# SHDN-CURRENT-S02-V00-Microcontroller.net
KiCad netlist of a schematic drawn in Altium Designer
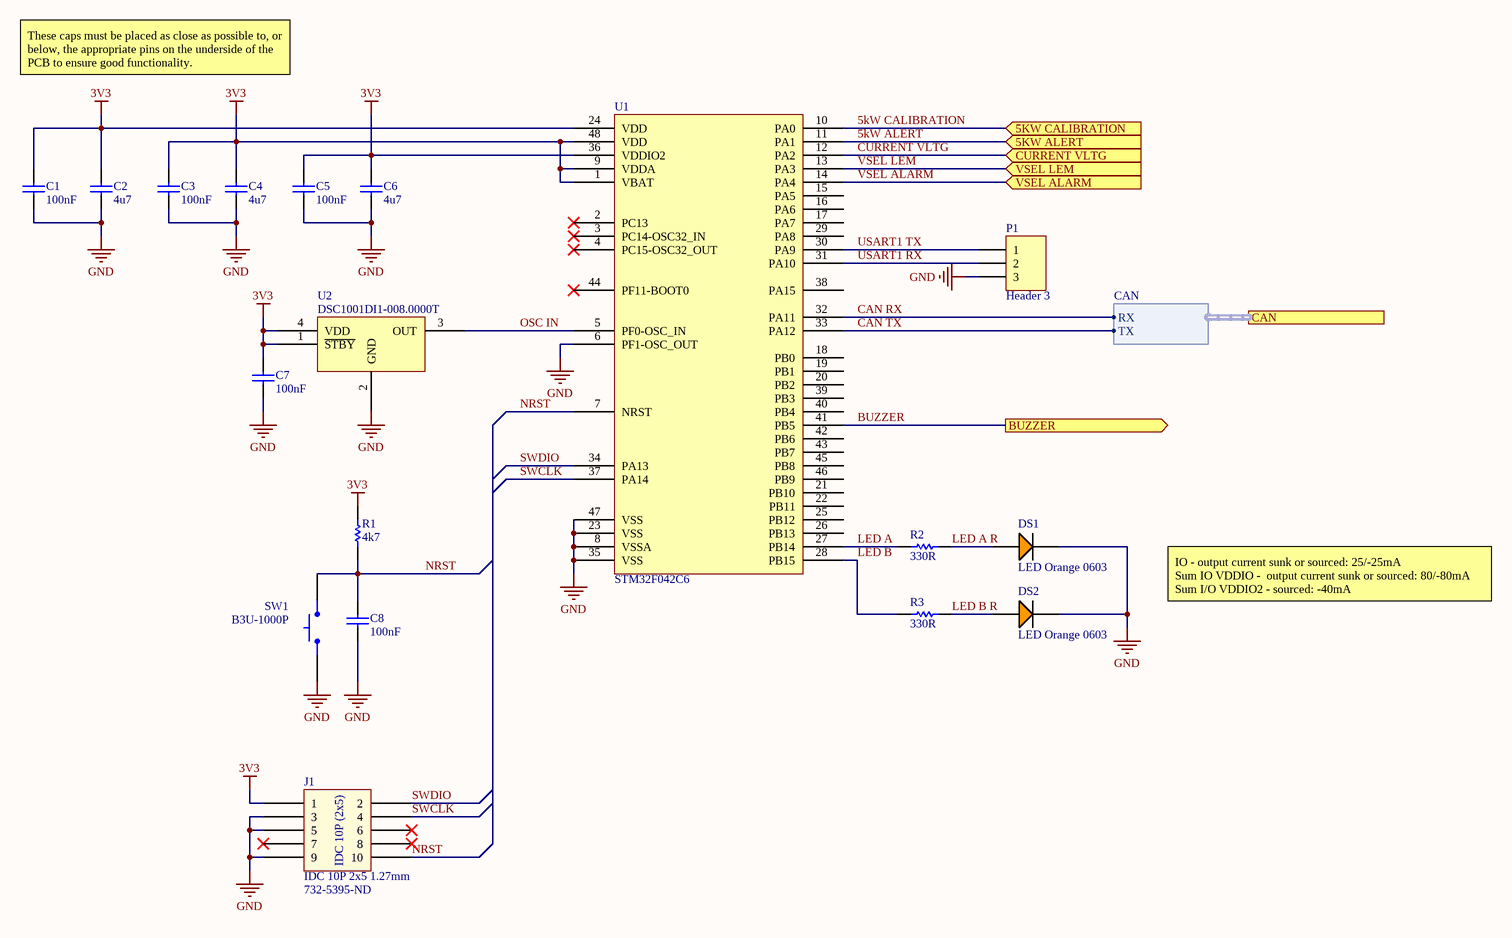
[diagram p0: SHDN-CURRENT-S02-V00-Microcontroller.SchDoc]

(export (version "E")
  (design (tool "Eeschema 10.0.6"))
  (components
    (comp (ref "C1")
      (value "100nF")
      (footprint "Cap_Ceramic_0603")
      (description "Capacitor, Ceramic, SMD, 100nF, 50V, 5%, X7R, 0603")
      (libsource (lib "StandardCapacitors") (part "100nF 50V 5% X7R 0603"))
    )
    (comp (ref "C2")
      (value "4u7")
      (footprint "Cap_Ceramic_0603")
      (description "Capacitor, Ceramic, SMD, 4u7, 50V, 5%, X7R, 0603")
      (libsource (lib "StandardCapacitors") (part "4u7 50V 5% X7R 0603"))
    )
    (comp (ref "C3")
      (value "100nF")
      (footprint "Cap_Ceramic_0603")
      (description "Capacitor, Ceramic, SMD, 100nF, 50V, 5%, X7R, 0603")
      (libsource (lib "StandardCapacitors") (part "100nF 50V 5% X7R 0603"))
    )
    (comp (ref "C4")
      (value "4u7")
      (footprint "Cap_Ceramic_0603")
      (description "Capacitor, Ceramic, SMD, 4u7, 50V, 5%, X7R, 0603")
      (libsource (lib "StandardCapacitors") (part "4u7 50V 5% X7R 0603"))
    )
    (comp (ref "C5")
      (value "100nF")
      (footprint "Cap_Ceramic_0603")
      (description "Capacitor, Ceramic, SMD, 100nF, 50V, 5%, X7R, 0603")
      (libsource (lib "StandardCapacitors") (part "100nF 50V 5% X7R 0603"))
    )
    (comp (ref "C6")
      (value "4u7")
      (footprint "Cap_Ceramic_0603")
      (description "Capacitor, Ceramic, SMD, 4u7, 50V, 5%, X7R, 0603")
      (libsource (lib "StandardCapacitors") (part "4u7 50V 5% X7R 0603"))
    )
    (comp (ref "C7")
      (value "100nF")
      (footprint "Cap_Ceramic_0603")
      (description "Capacitor, Ceramic, SMD, 100nF, 50V, 5%, X7R, 0603")
      (libsource (lib "StandardCapacitors") (part "100nF 50V 5% X7R 0603"))
    )
    (comp (ref "C8")
      (value "100nF")
      (footprint "Cap_Ceramic_0603")
      (description "Capacitor, Ceramic, SMD, 100nF, 50V, 5%, X7R, 0603")
      (libsource (lib "StandardCapacitors") (part "100nF 50V 5% X7R 0603"))
    )
    (comp (ref "DS1")
      (value "LED Orange 0603")
      (footprint "LED ORANGE 0603")
      (libsource (lib "QUTMS_LEDLibrary") (part "LED Orange 0603"))
    )
    (comp (ref "DS2")
      (value "LED Orange 0603")
      (footprint "LED ORANGE 0603")
      (libsource (lib "QUTMS_LEDLibrary") (part "LED Orange 0603"))
    )
    (comp (ref "J1")
      (value "IDC 10P 2x5 1.27mm")
      (footprint "IDC 1.27MM 10P")
      (libsource (lib "IDCConnectors") (part "IDC 10P 2x5 1.27mm"))
    )
    (comp (ref "P1")
      (value "Header 3")
      (footprint "HDR1X3")
      (description "Header, 3-Pin")
      (fields (field (name "PUBLISHER") "Altium Limited"))
      (libsource (lib "Miscellaneous Connectors") (part "Header 3"))
    )
    (comp (ref "R1")
      (value "4k7")
      (footprint "Res_ThinFilm_0603")
      (description "Resistor, SMD, 4k7, 0.1W, 5%, 0603")
      (libsource (lib "StandardResistors") (part "4k7 5% 0603"))
    )
    (comp (ref "R2")
      (value "330R")
      (footprint "Res_ThinFilm_0603")
      (description "Resistor, SMD, 330R, 0.1W, 5%, 0603")
      (libsource (lib "StandardResistors") (part "330R 5% 0603"))
    )
    (comp (ref "R3")
      (value "330R")
      (footprint "Res_ThinFilm_0603")
      (description "Resistor, SMD, 330R, 0.1W, 5%, 0603")
      (libsource (lib "StandardResistors") (part "330R 5% 0603"))
    )
    (comp (ref "SW1")
      (value "B3U-1000P")
      (footprint "BTN B3U-1000P")
      (description "Omron B3U-1000P Ultra Miniture Switch")
      (libsource (lib "QUTMS_SwitchLibrary") (part "BTN B3U-1000P"))
    )
    (comp (ref "U1")
      (value "STM32F042C6")
      (footprint "STM32F042C6")
      (description "ARM® Cortex®-M0 STM32F0 Microcontroller IC 32-Bit 48MHz 32KB (32K x 8) FLASH 48-LQFP (7x7)")
      (libsource (lib "QUTMS_STM32Library") (part "STM32F042C6"))
    )
    (comp (ref "U2")
      (value "DSC1001DI1-008.0000T")
      (footprint "DSC1001DI1-008.0000TCT-ND")
      (description "on 8MHz XO (Standard) CMOS Oscillator 1.8 ~ 3.3V Standby (Power Down) 4-SMD, No Lead")
      (libsource (lib "QUTMS_CrystalLibrary") (part "DSC1001DI1-008.0000T"))
    )
  )
  (nets
    (net (code "2") (name "/5kW ALERT") (class "Default")
      (node (ref "U1") (pin "11") (pinfunction "PA1_11") (pintype "passive"))
    )
    (net (code "3") (name "/5kW CALIBRATION") (class "Default")
      (node (ref "U1") (pin "10") (pinfunction "PA0_10") (pintype "passive"))
    )
    (net (code "4") (name "/BUZZER") (class "Default")
      (node (ref "U1") (pin "41") (pinfunction "PB5_41") (pintype "passive"))
    )
    (net (code "5") (name "/CAN RX") (class "Default")
      (node (ref "U1") (pin "32") (pinfunction "PA11_32") (pintype "passive"))
    )
    (net (code "6") (name "/CAN TX") (class "Default")
      (node (ref "U1") (pin "33") (pinfunction "PA12_33") (pintype "passive"))
    )
    (net (code "7") (name "/CURRENT VLTG") (class "Default")
      (node (ref "U1") (pin "12") (pinfunction "PA2_12") (pintype "passive"))
    )
    (net (code "8") (name "/LED A") (class "Default")
      (node (ref "R2") (pin "1") (pinfunction "1_1") (pintype "passive"))
      (node (ref "U1") (pin "27") (pinfunction "PB14_27") (pintype "passive"))
    )
    (net (code "9") (name "/LED A R") (class "Default")
      (node (ref "DS1") (pin "1") (pinfunction "A_1") (pintype "passive"))
      (node (ref "R2") (pin "2") (pinfunction "2_2") (pintype "passive"))
    )
    (net (code "10") (name "/LED B") (class "Default")
      (node (ref "R3") (pin "1") (pinfunction "1_1") (pintype "passive"))
      (node (ref "U1") (pin "28") (pinfunction "PB15_28") (pintype "passive"))
    )
    (net (code "11") (name "/LED B R") (class "Default")
      (node (ref "DS2") (pin "1") (pinfunction "A_1") (pintype "passive"))
      (node (ref "R3") (pin "2") (pinfunction "2_2") (pintype "passive"))
    )
    (net (code "12") (name "/NRST") (class "Default")
      (node (ref "C8") (pin "2") (pinfunction "2_2") (pintype "passive"))
      (node (ref "J1") (pin "10") (pinfunction "10_10") (pintype "passive"))
      (node (ref "R1") (pin "1") (pinfunction "1_1") (pintype "passive"))
      (node (ref "SW1") (pin "2") (pinfunction "2_2") (pintype "passive"))
      (node (ref "U1") (pin "7") (pinfunction "NRST_7") (pintype "passive"))
    )
    (net (code "13") (name "/OSC IN") (class "Default")
      (node (ref "U1") (pin "5") (pinfunction "PF0-OSC_IN_5") (pintype "passive"))
      (node (ref "U2") (pin "3") (pinfunction "OUT_3") (pintype "passive"))
    )
    (net (code "14") (name "/SWCLK") (class "Default")
      (node (ref "J1") (pin "4") (pinfunction "4_4") (pintype "passive"))
      (node (ref "U1") (pin "37") (pinfunction "PA14_37") (pintype "passive"))
    )
    (net (code "15") (name "/SWDIO") (class "Default")
      (node (ref "J1") (pin "2") (pinfunction "2_2") (pintype "passive"))
      (node (ref "U1") (pin "34") (pinfunction "PA13_34") (pintype "passive"))
    )
    (net (code "16") (name "/USART1 RX") (class "Default")
      (node (ref "P1") (pin "2") (pinfunction "2_2") (pintype "passive"))
      (node (ref "U1") (pin "31") (pinfunction "PA10_31") (pintype "passive"))
    )
    (net (code "17") (name "/USART1 TX") (class "Default")
      (node (ref "P1") (pin "1") (pinfunction "1_1") (pintype "passive"))
      (node (ref "U1") (pin "30") (pinfunction "PA9_30") (pintype "passive"))
    )
    (net (code "18") (name "/VSEL ALARM") (class "Default")
      (node (ref "U1") (pin "14") (pinfunction "PA4_14") (pintype "passive"))
    )
    (net (code "19") (name "/VSEL LEM") (class "Default")
      (node (ref "U1") (pin "13") (pinfunction "PA3_13") (pintype "passive"))
    )
    (net (code "21") (name "3V3") (class "Default")
      (node (ref "C1") (pin "2") (pinfunction "2_2") (pintype "passive"))
      (node (ref "C2") (pin "2") (pinfunction "2_2") (pintype "passive"))
      (node (ref "C3") (pin "2") (pinfunction "2_2") (pintype "passive"))
      (node (ref "C4") (pin "2") (pinfunction "2_2") (pintype "passive"))
      (node (ref "C5") (pin "2") (pinfunction "2_2") (pintype "passive"))
      (node (ref "C6") (pin "2") (pinfunction "2_2") (pintype "passive"))
      (node (ref "C7") (pin "2") (pinfunction "2_2") (pintype "passive"))
      (node (ref "J1") (pin "1") (pinfunction "1_1") (pintype "passive"))
      (node (ref "R1") (pin "2") (pinfunction "2_2") (pintype "passive"))
      (node (ref "U1") (pin "1") (pinfunction "VBAT_1") (pintype "passive"))
      (node (ref "U1") (pin "24") (pinfunction "VDD_24") (pintype "passive"))
      (node (ref "U1") (pin "36") (pinfunction "VDDIO2_36") (pintype "passive"))
      (node (ref "U1") (pin "48") (pinfunction "VDD_48") (pintype "passive"))
      (node (ref "U1") (pin "9") (pinfunction "VDDA_9") (pintype "passive"))
      (node (ref "U2") (pin "1") (pinfunction "~{STBY}_1") (pintype "passive"))
      (node (ref "U2") (pin "4") (pinfunction "VDD_4") (pintype "passive"))
    )
    (net (code "22") (name "GND") (class "Default")
      (node (ref "C1") (pin "1") (pinfunction "1_1") (pintype "passive"))
      (node (ref "C2") (pin "1") (pinfunction "1_1") (pintype "passive"))
      (node (ref "C3") (pin "1") (pinfunction "1_1") (pintype "passive"))
      (node (ref "C4") (pin "1") (pinfunction "1_1") (pintype "passive"))
      (node (ref "C5") (pin "1") (pinfunction "1_1") (pintype "passive"))
      (node (ref "C6") (pin "1") (pinfunction "1_1") (pintype "passive"))
      (node (ref "C7") (pin "1") (pinfunction "1_1") (pintype "passive"))
      (node (ref "C8") (pin "1") (pinfunction "1_1") (pintype "passive"))
      (node (ref "DS1") (pin "2") (pinfunction "C_2") (pintype "passive"))
      (node (ref "DS2") (pin "2") (pinfunction "C_2") (pintype "passive"))
      (node (ref "J1") (pin "3") (pinfunction "3_3") (pintype "passive"))
      (node (ref "J1") (pin "5") (pinfunction "5_5") (pintype "passive"))
      (node (ref "J1") (pin "9") (pinfunction "9_9") (pintype "passive"))
      (node (ref "P1") (pin "3") (pinfunction "3_3") (pintype "passive"))
      (node (ref "SW1") (pin "1") (pinfunction "1_1") (pintype "passive"))
      (node (ref "U1") (pin "23") (pinfunction "VSS_23") (pintype "passive"))
      (node (ref "U1") (pin "35") (pinfunction "VSS_35") (pintype "passive"))
      (node (ref "U1") (pin "47") (pinfunction "VSS_47") (pintype "passive"))
      (node (ref "U1") (pin "6") (pinfunction "PF1-OSC_OUT_6") (pintype "passive"))
      (node (ref "U1") (pin "8") (pinfunction "VSSA_8") (pintype "passive"))
      (node (ref "U2") (pin "2") (pinfunction "GND_2") (pintype "passive"))
    )
    (net (code "23") (name "unconnected-(J1-Pad6)") (class "Default")
      (node (ref "J1") (pin "6") (pinfunction "6_6") (pintype "passive+no_connect"))
    )
    (net (code "24") (name "unconnected-(J1-Pad7)") (class "Default")
      (node (ref "J1") (pin "7") (pinfunction "7_7") (pintype "passive+no_connect"))
    )
    (net (code "25") (name "unconnected-(J1-Pad8)") (class "Default")
      (node (ref "J1") (pin "8") (pinfunction "8_8") (pintype "passive+no_connect"))
    )
    (net (code "26") (name "unconnected-(U1-PA5-Pad15)") (class "Default")
      (node (ref "U1") (pin "15") (pinfunction "PA5_15") (pintype "passive"))
    )
    (net (code "27") (name "unconnected-(U1-PA6-Pad16)") (class "Default")
      (node (ref "U1") (pin "16") (pinfunction "PA6_16") (pintype "passive"))
    )
    (net (code "28") (name "unconnected-(U1-PA7-Pad17)") (class "Default")
      (node (ref "U1") (pin "17") (pinfunction "PA7_17") (pintype "passive"))
    )
    (net (code "29") (name "unconnected-(U1-PA8-Pad29)") (class "Default")
      (node (ref "U1") (pin "29") (pinfunction "PA8_29") (pintype "passive"))
    )
    (net (code "30") (name "unconnected-(U1-PA15-Pad38)") (class "Default")
      (node (ref "U1") (pin "38") (pinfunction "PA15_38") (pintype "passive"))
    )
    (net (code "31") (name "unconnected-(U1-PB0-Pad18)") (class "Default")
      (node (ref "U1") (pin "18") (pinfunction "PB0_18") (pintype "passive"))
    )
    (net (code "32") (name "unconnected-(U1-PB1-Pad19)") (class "Default")
      (node (ref "U1") (pin "19") (pinfunction "PB1_19") (pintype "passive"))
    )
    (net (code "33") (name "unconnected-(U1-PB2-Pad20)") (class "Default")
      (node (ref "U1") (pin "20") (pinfunction "PB2_20") (pintype "passive"))
    )
    (net (code "34") (name "unconnected-(U1-PB3-Pad39)") (class "Default")
      (node (ref "U1") (pin "39") (pinfunction "PB3_39") (pintype "passive"))
    )
    (net (code "35") (name "unconnected-(U1-PB4-Pad40)") (class "Default")
      (node (ref "U1") (pin "40") (pinfunction "PB4_40") (pintype "passive"))
    )
    (net (code "36") (name "unconnected-(U1-PB6-Pad42)") (class "Default")
      (node (ref "U1") (pin "42") (pinfunction "PB6_42") (pintype "passive"))
    )
    (net (code "37") (name "unconnected-(U1-PB7-Pad43)") (class "Default")
      (node (ref "U1") (pin "43") (pinfunction "PB7_43") (pintype "passive"))
    )
    (net (code "38") (name "unconnected-(U1-PB8-Pad45)") (class "Default")
      (node (ref "U1") (pin "45") (pinfunction "PB8_45") (pintype "passive"))
    )
    (net (code "39") (name "unconnected-(U1-PB9-Pad46)") (class "Default")
      (node (ref "U1") (pin "46") (pinfunction "PB9_46") (pintype "passive"))
    )
    (net (code "40") (name "unconnected-(U1-PB10-Pad21)") (class "Default")
      (node (ref "U1") (pin "21") (pinfunction "PB10_21") (pintype "passive"))
    )
    (net (code "41") (name "unconnected-(U1-PB11-Pad22)") (class "Default")
      (node (ref "U1") (pin "22") (pinfunction "PB11_22") (pintype "passive"))
    )
    (net (code "42") (name "unconnected-(U1-PB12-Pad25)") (class "Default")
      (node (ref "U1") (pin "25") (pinfunction "PB12_25") (pintype "passive"))
    )
    (net (code "43") (name "unconnected-(U1-PB13-Pad26)") (class "Default")
      (node (ref "U1") (pin "26") (pinfunction "PB13_26") (pintype "passive"))
    )
    (net (code "44") (name "unconnected-(U1-PC13-Pad2)") (class "Default")
      (node (ref "U1") (pin "2") (pinfunction "PC13_2") (pintype "passive+no_connect"))
    )
    (net (code "45") (name "unconnected-(U1-PC14-OSC32_IN-Pad3)") (class "Default")
      (node (ref "U1") (pin "3") (pinfunction "PC14-OSC32_IN_3") (pintype "passive+no_connect"))
    )
    (net (code "46") (name "unconnected-(U1-PC15-OSC32_OUT-Pad4)") (class "Default")
      (node (ref "U1") (pin "4") (pinfunction "PC15-OSC32_OUT_4") (pintype "passive+no_connect"))
    )
    (net (code "47") (name "unconnected-(U1-PF11-BOOT0-Pad44)") (class "Default")
      (node (ref "U1") (pin "44") (pinfunction "PF11-BOOT0_44") (pintype "passive+no_connect"))
    )
  )
)
